# CHECON_PCB_Button.net
KiCad netlist of a schematic drawn in EAGLE
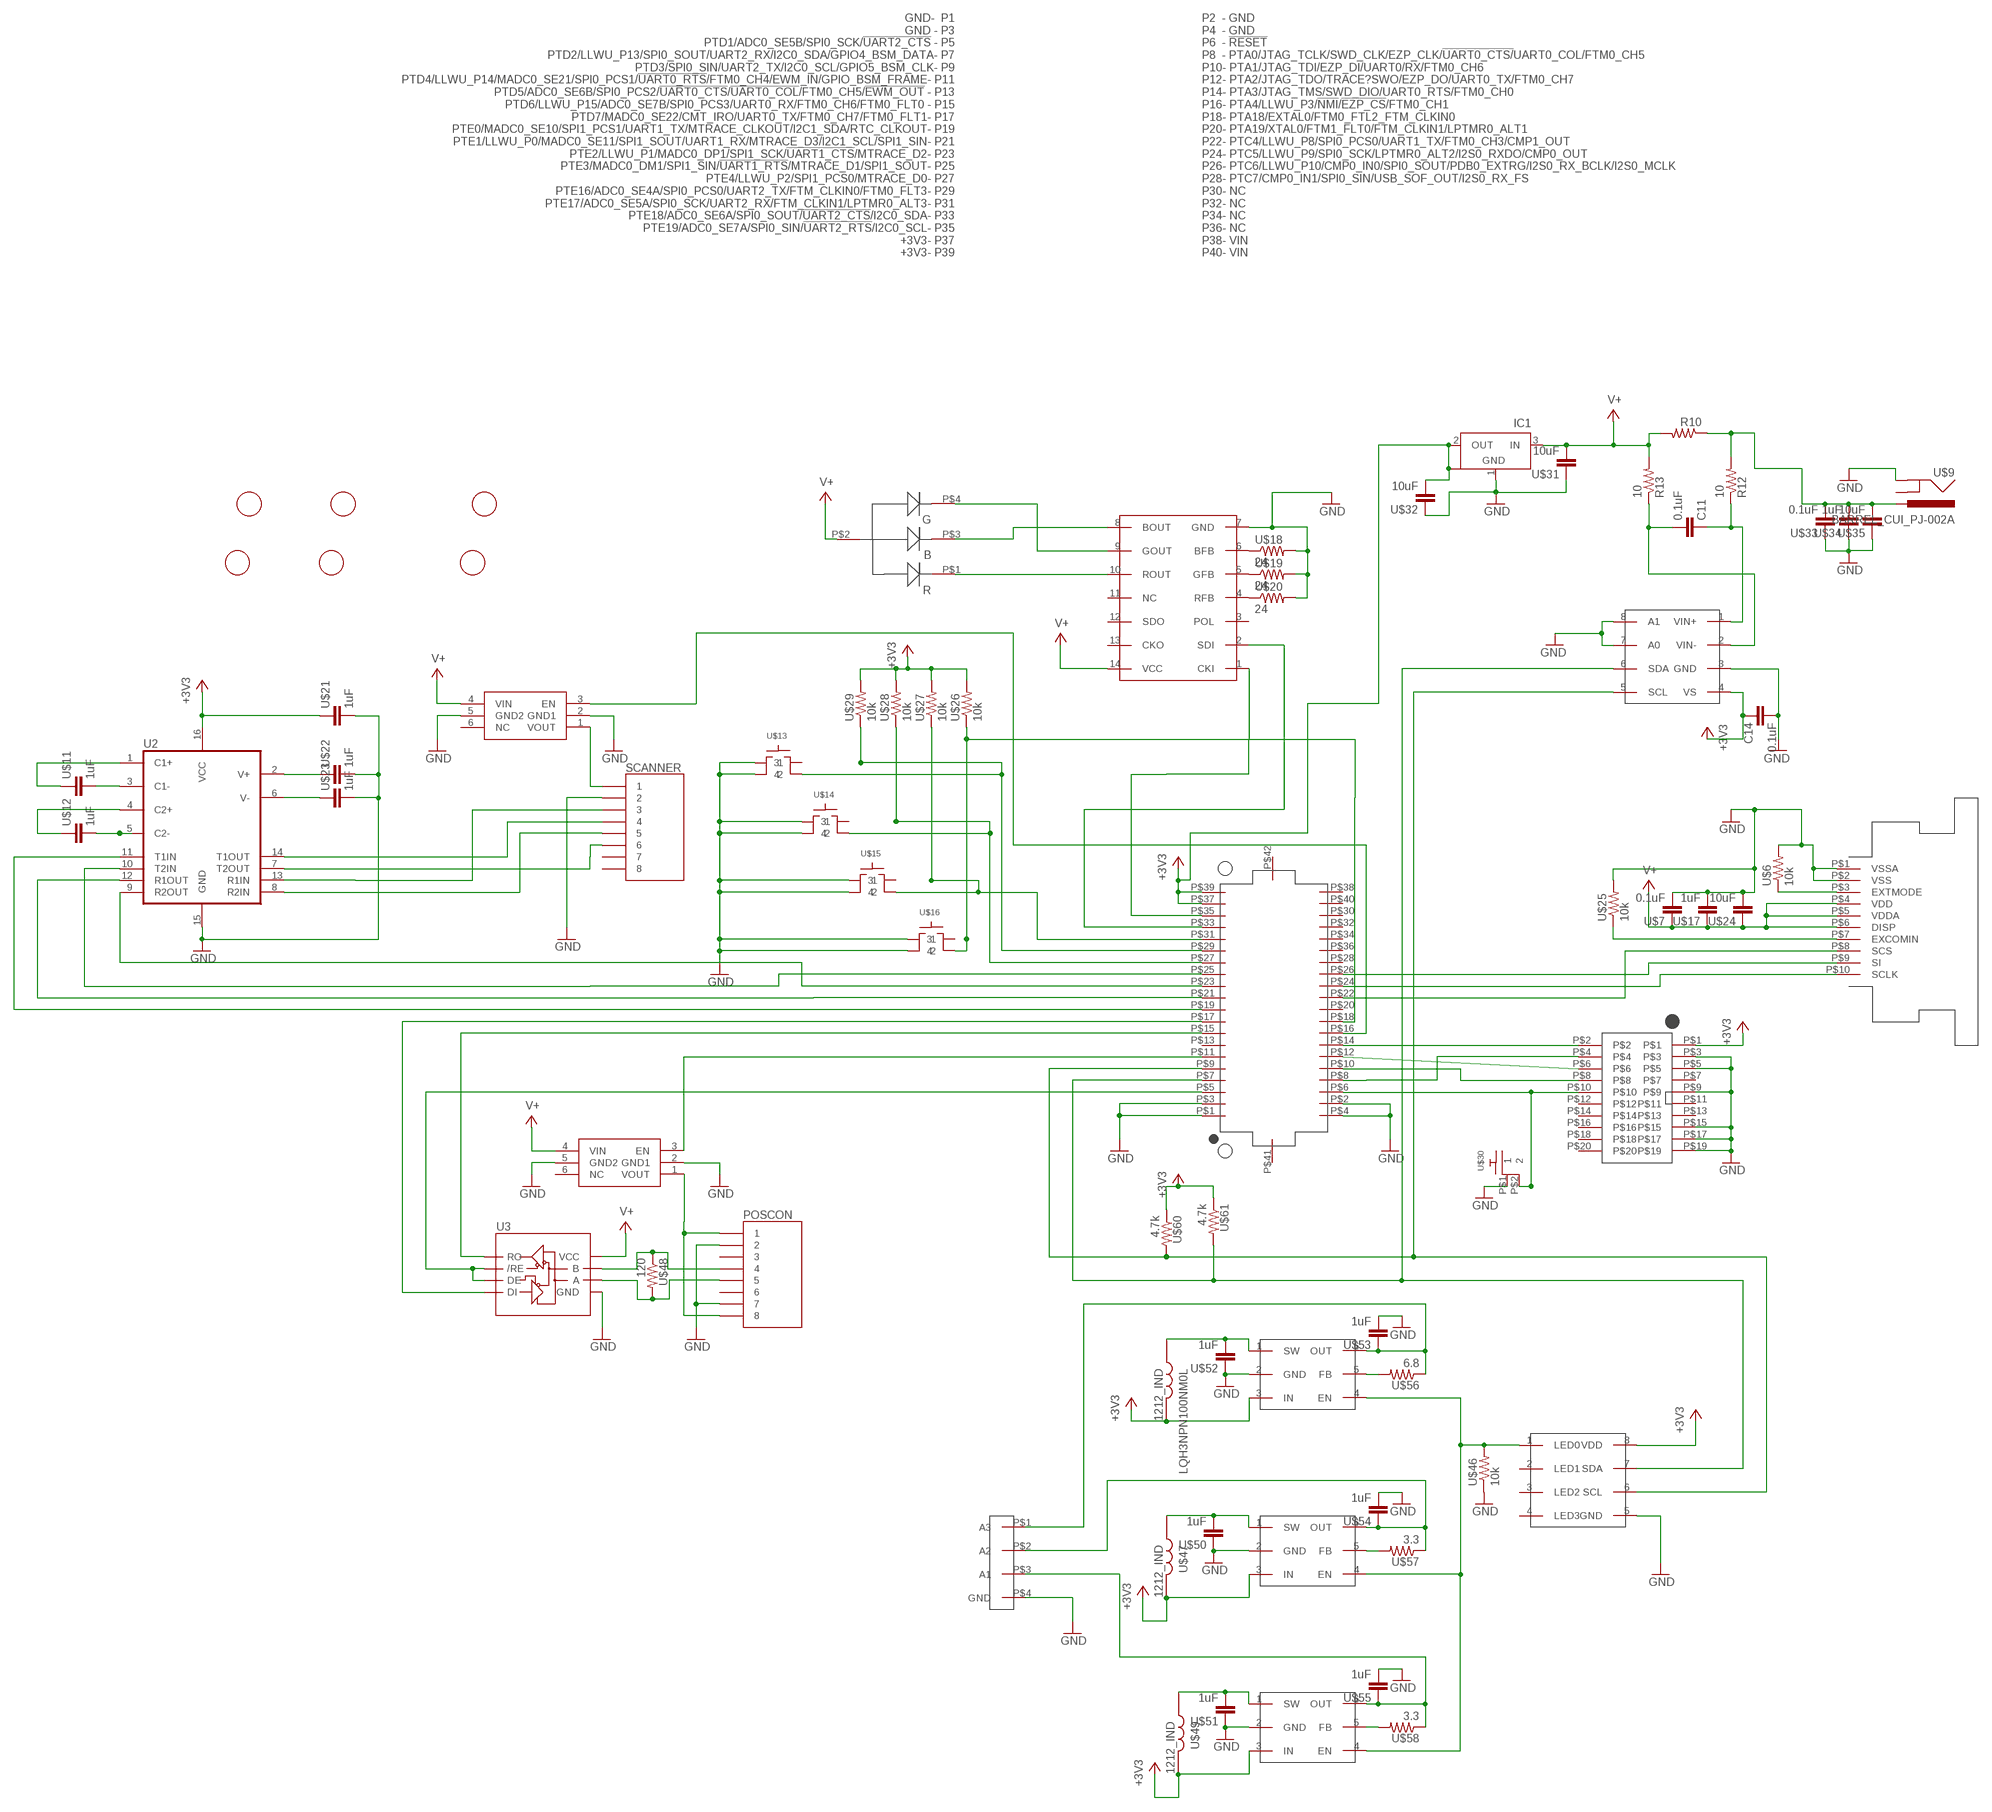
[diagram p0: schematic, sheet 1]

(export (version "E")
  (design (tool "Eeschema 10.0.6"))
  (components
    (comp (ref "C11")
      (value "0.1uF")
      (footprint "eagle-import:C0805")
      (libsource (lib "eagle-import") (part "RF-C0805"))
    )
    (comp (ref "C14")
      (value "0.1uF")
      (footprint "eagle-import:C0805")
      (libsource (lib "eagle-import") (part "RF-C0805"))
    )
    (comp (ref "IC1")
      (value "NCP1117ST33T3G_1")
      (footprint "eagle-import:SOT223")
      (libsource (lib "eagle-import") (part "NCP1117ST33T3G_1"))
    )
    (comp (ref "LQH3NPN100NM0L")
      (value "1212_IND")
      (footprint "eagle-import:1212_IND")
      (libsource (lib "eagle-import") (part "1212_IND"))
    )
    (comp (ref "POSCON")
      (value "RJ45-8")
      (footprint "eagle-import:RJ45_SMD")
      (fields (field (name "MFGN") "Molex") (field (name "MFGP") "0955016889"))
      (libsource (lib "eagle-import") (part "RJ45-8"))
    )
    (comp (ref "R10")
      (value "RF-R2512")
      (footprint "eagle-import:R2512")
      (libsource (lib "eagle-import") (part "RF-R2512"))
    )
    (comp (ref "R12")
      (value "10")
      (footprint "eagle-import:RF-C0805")
      (libsource (lib "eagle-import") (part "RF-R0805"))
    )
    (comp (ref "R13")
      (value "10")
      (footprint "eagle-import:RF-C0805")
      (libsource (lib "eagle-import") (part "RF-R0805"))
    )
    (comp (ref "SCANNER")
      (value "RJ45-8")
      (footprint "eagle-import:RJ45_SMD")
      (fields (field (name "MFGP") "0955016889"))
      (libsource (lib "eagle-import") (part "RJ45-8"))
    )
    (comp (ref "U$1")
      (value "RGLBED")
      (footprint "eagle-import:RGBLED")
      (libsource (lib "eagle-import") (part "RGLBED"))
    )
    (comp (ref "U$2")
      (value "52745-1097")
      (footprint "eagle-import:52745-1097")
      (libsource (lib "eagle-import") (part "52745-1097"))
    )
    (comp (ref "U$3")
      (value "2X10JTAG")
      (footprint "eagle-import:2X10JTAG")
      (libsource (lib "eagle-import") (part "2X10JTAG"))
    )
    (comp (ref "U$4")
      (value "MIC94061C6")
      (footprint "eagle-import:SC70-6L")
      (libsource (lib "eagle-import") (part "MIC94061C6"))
    )
    (comp (ref "U$5")
      (value "MIC94061C6")
      (footprint "eagle-import:SC70-6L")
      (libsource (lib "eagle-import") (part "MIC94061C6"))
    )
    (comp (ref "U$6")
      (value "10k")
      (footprint "eagle-import:RF-C0805")
      (libsource (lib "eagle-import") (part "RF-R0805"))
    )
    (comp (ref "U$7")
      (value "0.1uF")
      (footprint "eagle-import:C0805")
      (libsource (lib "eagle-import") (part "RF-C0805"))
    )
    (comp (ref "U$8")
      (value "WS2801")
      (footprint "eagle-import:SO14")
      (fields (field (name "MFGP") "WS2801"))
      (libsource (lib "eagle-import") (part "WS2801"))
    )
    (comp (ref "U$9")
      (value "BARREL_CUI_PJ-002A")
      (footprint "eagle-import:BARREL_CUI_PJ-002A")
      (libsource (lib "eagle-import") (part "BARREL_CUI_PJ-002A"))
    )
    (comp (ref "U$10")
      (value "KW2_CPU_COMBO")
      (footprint "eagle-import:BRAIN_COMBO")
      (libsource (lib "eagle-import") (part "KW2_CPU_COMBO"))
    )
    (comp (ref "U$11")
      (value "1uF")
      (footprint "eagle-import:C0805")
      (libsource (lib "eagle-import") (part "RF-C0805"))
    )
    (comp (ref "U$12")
      (value "1uF")
      (footprint "eagle-import:C0805")
      (libsource (lib "eagle-import") (part "RF-C0805"))
    )
    (comp (ref "U$13")
      (value "SWITCH-TACTILE-FSM")
      (footprint "eagle-import:SWITCH-TACTILE-FSM")
      (libsource (lib "eagle-import") (part "SWITCH-TACTILE-FSM"))
    )
    (comp (ref "U$14")
      (value "SWITCH-TACTILE-FSM")
      (footprint "eagle-import:SWITCH-TACTILE-FSM")
      (libsource (lib "eagle-import") (part "SWITCH-TACTILE-FSM"))
    )
    (comp (ref "U$15")
      (value "SWITCH-TACTILE-FSM")
      (footprint "eagle-import:SWITCH-TACTILE-FSM")
      (libsource (lib "eagle-import") (part "SWITCH-TACTILE-FSM"))
    )
    (comp (ref "U$16")
      (value "SWITCH-TACTILE-FSM")
      (footprint "eagle-import:SWITCH-TACTILE-FSM")
      (libsource (lib "eagle-import") (part "SWITCH-TACTILE-FSM"))
    )
    (comp (ref "U$17")
      (value "1uF")
      (footprint "eagle-import:C0805")
      (libsource (lib "eagle-import") (part "RF-C0805"))
    )
    (comp (ref "U$18")
      (value "24")
      (footprint "eagle-import:RF-C0805")
      (libsource (lib "eagle-import") (part "RF-R0805"))
    )
    (comp (ref "U$19")
      (value "24")
      (footprint "eagle-import:RF-C0805")
      (libsource (lib "eagle-import") (part "RF-R0805"))
    )
    (comp (ref "U$20")
      (value "24")
      (footprint "eagle-import:RF-C0805")
      (libsource (lib "eagle-import") (part "RF-R0805"))
    )
    (comp (ref "U$21")
      (value "1uF")
      (footprint "eagle-import:C0805")
      (libsource (lib "eagle-import") (part "RF-C0805"))
    )
    (comp (ref "U$22")
      (value "1uF")
      (footprint "eagle-import:C0805")
      (libsource (lib "eagle-import") (part "RF-C0805"))
    )
    (comp (ref "U$23")
      (value "1uF")
      (footprint "eagle-import:C0805")
      (libsource (lib "eagle-import") (part "RF-C0805"))
    )
    (comp (ref "U$24")
      (value "10uF")
      (footprint "eagle-import:C0805")
      (libsource (lib "eagle-import") (part "RF-C0805"))
    )
    (comp (ref "U$25")
      (value "10k")
      (footprint "eagle-import:RF-C0805")
      (libsource (lib "eagle-import") (part "RF-R0805"))
    )
    (comp (ref "U$26")
      (value "10k")
      (footprint "eagle-import:RF-C0805")
      (libsource (lib "eagle-import") (part "RF-R0805"))
    )
    (comp (ref "U$27")
      (value "10k")
      (footprint "eagle-import:RF-C0805")
      (libsource (lib "eagle-import") (part "RF-R0805"))
    )
    (comp (ref "U$28")
      (value "10k")
      (footprint "eagle-import:RF-C0805")
      (libsource (lib "eagle-import") (part "RF-R0805"))
    )
    (comp (ref "U$29")
      (value "10k")
      (footprint "eagle-import:RF-C0805")
      (libsource (lib "eagle-import") (part "RF-R0805"))
    )
    (comp (ref "U$30")
      (value "RA_BUTTON")
      (footprint "eagle-import:RA_BUTTON")
      (libsource (lib "eagle-import") (part "RA_BUTTON"))
    )
    (comp (ref "U$31")
      (value "10uF")
      (footprint "eagle-import:C0805")
      (libsource (lib "eagle-import") (part "RF-C0805"))
    )
    (comp (ref "U$32")
      (value "10uF")
      (footprint "eagle-import:C0805")
      (libsource (lib "eagle-import") (part "RF-C0805"))
    )
    (comp (ref "U$33")
      (value "0.1uF")
      (footprint "eagle-import:C0805")
      (libsource (lib "eagle-import") (part "RF-C0805"))
    )
    (comp (ref "U$34")
      (value "1uF")
      (footprint "eagle-import:C0805")
      (libsource (lib "eagle-import") (part "RF-C0805"))
    )
    (comp (ref "U$35")
      (value "10uF")
      (footprint "eagle-import:C0805")
      (libsource (lib "eagle-import") (part "RF-C0805"))
    )
    (comp (ref "U$36")
      (value "SC4541")
      (footprint "eagle-import:SOT23-6")
      (libsource (lib "eagle-import") (part "SC4541"))
    )
    (comp (ref "U$37")
      (value "SC4541")
      (footprint "eagle-import:SOT23-6")
      (libsource (lib "eagle-import") (part "SC4541"))
    )
    (comp (ref "U$38")
      (value "FIDUCIAL")
      (footprint "eagle-import:FIDUCIAL_1MM")
      (libsource (lib "eagle-import") (part "FIDUCIAL"))
    )
    (comp (ref "U$39")
      (value "FIDUCIAL")
      (footprint "eagle-import:FIDUCIAL_1MM")
      (libsource (lib "eagle-import") (part "FIDUCIAL"))
    )
    (comp (ref "U$40")
      (value "FIDUCIAL")
      (footprint "eagle-import:FIDUCIAL_1MM")
      (libsource (lib "eagle-import") (part "FIDUCIAL"))
    )
    (comp (ref "U$41")
      (value "FIDUCIAL")
      (footprint "eagle-import:FIDUCIAL_1MM")
      (libsource (lib "eagle-import") (part "FIDUCIAL"))
    )
    (comp (ref "U$42")
      (value "FIDUCIAL")
      (footprint "eagle-import:FIDUCIAL_1MM")
      (libsource (lib "eagle-import") (part "FIDUCIAL"))
    )
    (comp (ref "U$43")
      (value "FIDUCIAL")
      (footprint "eagle-import:FIDUCIAL_1MM")
      (libsource (lib "eagle-import") (part "FIDUCIAL"))
    )
    (comp (ref "U$44")
      (value "SC4541")
      (footprint "eagle-import:SOT23-6")
      (libsource (lib "eagle-import") (part "SC4541"))
    )
    (comp (ref "U$45")
      (value "PCA9632DP1")
      (footprint "eagle-import:TSSOP-8")
      (libsource (lib "eagle-import") (part "PCA9632DP1"))
    )
    (comp (ref "U$46")
      (value "10k")
      (footprint "eagle-import:RF-C0805")
      (libsource (lib "eagle-import") (part "RF-R0805"))
    )
    (comp (ref "U$47")
      (value "1212_IND")
      (footprint "eagle-import:1212_IND")
      (libsource (lib "eagle-import") (part "1212_IND"))
    )
    (comp (ref "U$48")
      (value "120")
      (footprint "eagle-import:RF-C0805")
      (libsource (lib "eagle-import") (part "RF-R0805"))
    )
    (comp (ref "U$49")
      (value "1212_IND")
      (footprint "eagle-import:1212_IND")
      (libsource (lib "eagle-import") (part "1212_IND"))
    )
    (comp (ref "U$50")
      (value "1uF")
      (footprint "eagle-import:C0805")
      (libsource (lib "eagle-import") (part "RF-C0805"))
    )
    (comp (ref "U$51")
      (value "1uF")
      (footprint "eagle-import:C0805")
      (libsource (lib "eagle-import") (part "RF-C0805"))
    )
    (comp (ref "U$52")
      (value "1uF")
      (footprint "eagle-import:C0805")
      (libsource (lib "eagle-import") (part "RF-C0805"))
    )
    (comp (ref "U$53")
      (value "1uF")
      (footprint "eagle-import:C0805")
      (libsource (lib "eagle-import") (part "RF-C0805"))
    )
    (comp (ref "U$54")
      (value "1uF")
      (footprint "eagle-import:C0805")
      (libsource (lib "eagle-import") (part "RF-C0805"))
    )
    (comp (ref "U$55")
      (value "1uF")
      (footprint "eagle-import:C0805")
      (libsource (lib "eagle-import") (part "RF-C0805"))
    )
    (comp (ref "U$56")
      (value "6.8")
      (footprint "eagle-import:RF-C0805")
      (libsource (lib "eagle-import") (part "RF-R0805"))
    )
    (comp (ref "U$57")
      (value "3.3")
      (footprint "eagle-import:RF-C0805")
      (libsource (lib "eagle-import") (part "RF-R0805"))
    )
    (comp (ref "U$58")
      (value "3.3")
      (footprint "eagle-import:RF-C0805")
      (libsource (lib "eagle-import") (part "RF-R0805"))
    )
    (comp (ref "U$59")
      (value "BL_CON")
      (footprint "eagle-import:009155004301006")
      (libsource (lib "eagle-import") (part "BL_CON"))
    )
    (comp (ref "U$60")
      (value "4.7k")
      (footprint "eagle-import:RF-C0805")
      (libsource (lib "eagle-import") (part "RF-R0805"))
    )
    (comp (ref "U$61")
      (value "4.7k")
      (footprint "eagle-import:RF-C0805")
      (libsource (lib "eagle-import") (part "RF-R0805"))
    )
    (comp (ref "U$62")
      (value "INA219B")
      (footprint "eagle-import:DCN-R-PDSO-G8")
      (libsource (lib "eagle-import") (part "INA219B"))
    )
    (comp (ref "U2")
      (value "MAX232SOIC16")
      (footprint "eagle-import:SO016")
      (fields (field (name "MFGP") "MAX232DR"))
      (libsource (lib "eagle-import") (part "MAX232SOIC16"))
    )
    (comp (ref "U3")
      (value "RS485SOIC")
      (footprint "eagle-import:SO08")
      (fields (field (name "MFGP") "SN65HVD1781DR"))
      (libsource (lib "eagle-import") (part "RS485SOIC"))
    )
  )
  (nets
    (net (code "1") (name "+3V3") (class "Default")
      (node (ref "C14") (pin "1") (pinfunction "1_1") (pintype "passive"))
      (node (ref "IC1") (pin "2") (pinfunction "OUT_2") (pintype "power_in"))
      (node (ref "IC1") (pin "4") (pinfunction "OUT1_4") (pintype "power_in"))
      (node (ref "LQH3NPN100NM0L") (pin "P$1") (pinfunction "1_P$1") (pintype "bidirectional"))
      (node (ref "U$10") (pin "P$37") (pinfunction "+3V3_P$37") (pintype "bidirectional"))
      (node (ref "U$10") (pin "P$39") (pinfunction "+3V3_P$39") (pintype "bidirectional"))
      (node (ref "U$21") (pin "1") (pinfunction "1_1") (pintype "passive"))
      (node (ref "U$26") (pin "2") (pinfunction "2_2") (pintype "passive"))
      (node (ref "U$27") (pin "2") (pinfunction "2_2") (pintype "passive"))
      (node (ref "U$28") (pin "2") (pinfunction "2_2") (pintype "passive"))
      (node (ref "U$29") (pin "2") (pinfunction "2_2") (pintype "passive"))
      (node (ref "U$3") (pin "P$1") (pinfunction "P$1_P$1") (pintype "bidirectional"))
      (node (ref "U$32") (pin "2") (pinfunction "2_2") (pintype "passive"))
      (node (ref "U$36") (pin "3") (pinfunction "IN_3") (pintype "bidirectional"))
      (node (ref "U$37") (pin "3") (pinfunction "IN_3") (pintype "bidirectional"))
      (node (ref "U$44") (pin "3") (pinfunction "IN_3") (pintype "bidirectional"))
      (node (ref "U$45") (pin "8") (pinfunction "VDD_8") (pintype "bidirectional"))
      (node (ref "U$47") (pin "P$1") (pinfunction "1_P$1") (pintype "bidirectional"))
      (node (ref "U$49") (pin "P$1") (pinfunction "1_P$1") (pintype "bidirectional"))
      (node (ref "U$60") (pin "1") (pinfunction "1_1") (pintype "passive"))
      (node (ref "U$61") (pin "1") (pinfunction "1_1") (pintype "passive"))
      (node (ref "U$62") (pin "4") (pinfunction "VS_4") (pintype "bidirectional"))
      (node (ref "U2") (pin "16") (pinfunction "VCC_16") (pintype "bidirectional"))
    )
    (net (code "2") (name "GND") (class "Default")
      (node (ref "C14") (pin "2") (pinfunction "2_2") (pintype "passive"))
      (node (ref "IC1") (pin "1") (pinfunction "GND_1") (pintype "power_in"))
      (node (ref "POSCON") (pin "P$2") (pinfunction "2_P$2") (pintype "bidirectional"))
      (node (ref "POSCON") (pin "P$7") (pinfunction "7_P$7") (pintype "bidirectional"))
      (node (ref "SCANNER") (pin "P$2") (pinfunction "2_P$2") (pintype "bidirectional"))
      (node (ref "U$10") (pin "P$1") (pinfunction "GND_P$1") (pintype "bidirectional"))
      (node (ref "U$10") (pin "P$2") (pinfunction "GND_P$2") (pintype "bidirectional"))
      (node (ref "U$10") (pin "P$3") (pinfunction "GND_P$3") (pintype "bidirectional"))
      (node (ref "U$10") (pin "P$4") (pinfunction "GND_P$4") (pintype "bidirectional"))
      (node (ref "U$13") (pin "P$1") (pinfunction "1_P$1") (pintype "input"))
      (node (ref "U$13") (pin "P$2") (pinfunction "2_P$2") (pintype "input"))
      (node (ref "U$14") (pin "P$1") (pinfunction "1_P$1") (pintype "input"))
      (node (ref "U$14") (pin "P$2") (pinfunction "2_P$2") (pintype "input"))
      (node (ref "U$15") (pin "P$1") (pinfunction "1_P$1") (pintype "input"))
      (node (ref "U$15") (pin "P$2") (pinfunction "2_P$2") (pintype "input"))
      (node (ref "U$16") (pin "P$1") (pinfunction "1_P$1") (pintype "input"))
      (node (ref "U$16") (pin "P$2") (pinfunction "2_P$2") (pintype "input"))
      (node (ref "U$17") (pin "2") (pinfunction "2_2") (pintype "passive"))
      (node (ref "U$18") (pin "2") (pinfunction "2_2") (pintype "passive"))
      (node (ref "U$19") (pin "2") (pinfunction "2_2") (pintype "passive"))
      (node (ref "U$2") (pin "P$1") (pinfunction "VSSA_P$1") (pintype "bidirectional"))
      (node (ref "U$2") (pin "P$2") (pinfunction "VSS_P$2") (pintype "bidirectional"))
      (node (ref "U$20") (pin "2") (pinfunction "2_2") (pintype "passive"))
      (node (ref "U$21") (pin "2") (pinfunction "2_2") (pintype "passive"))
      (node (ref "U$22") (pin "2") (pinfunction "2_2") (pintype "passive"))
      (node (ref "U$23") (pin "2") (pinfunction "2_2") (pintype "passive"))
      (node (ref "U$24") (pin "2") (pinfunction "2_2") (pintype "passive"))
      (node (ref "U$25") (pin "2") (pinfunction "2_2") (pintype "passive"))
      (node (ref "U$3") (pin "P$15") (pinfunction "P$15_P$15") (pintype "bidirectional"))
      (node (ref "U$3") (pin "P$17") (pinfunction "P$17_P$17") (pintype "bidirectional"))
      (node (ref "U$3") (pin "P$19") (pinfunction "P$19_P$19") (pintype "bidirectional"))
      (node (ref "U$3") (pin "P$3") (pinfunction "P$3_P$3") (pintype "bidirectional"))
      (node (ref "U$3") (pin "P$5") (pinfunction "P$5_P$5") (pintype "bidirectional"))
      (node (ref "U$3") (pin "P$9") (pinfunction "P$9_P$9") (pintype "bidirectional"))
      (node (ref "U$30") (pin "P$1") (pinfunction "1_P$1") (pintype "input"))
      (node (ref "U$31") (pin "1") (pinfunction "1_1") (pintype "passive"))
      (node (ref "U$32") (pin "1") (pinfunction "1_1") (pintype "passive"))
      (node (ref "U$33") (pin "1") (pinfunction "1_1") (pintype "passive"))
      (node (ref "U$34") (pin "1") (pinfunction "1_1") (pintype "passive"))
      (node (ref "U$35") (pin "1") (pinfunction "1_1") (pintype "passive"))
      (node (ref "U$36") (pin "2") (pinfunction "GND_2") (pintype "bidirectional"))
      (node (ref "U$37") (pin "2") (pinfunction "GND_2") (pintype "bidirectional"))
      (node (ref "U$4") (pin "2") (pinfunction "GND1_2") (pintype "bidirectional"))
      (node (ref "U$4") (pin "5") (pinfunction "GND2_5") (pintype "bidirectional"))
      (node (ref "U$44") (pin "2") (pinfunction "GND_2") (pintype "bidirectional"))
      (node (ref "U$45") (pin "5") (pinfunction "GND_5") (pintype "bidirectional"))
      (node (ref "U$46") (pin "1") (pinfunction "1_1") (pintype "passive"))
      (node (ref "U$5") (pin "2") (pinfunction "GND1_2") (pintype "bidirectional"))
      (node (ref "U$5") (pin "5") (pinfunction "GND2_5") (pintype "bidirectional"))
      (node (ref "U$50") (pin "1") (pinfunction "1_1") (pintype "passive"))
      (node (ref "U$51") (pin "1") (pinfunction "1_1") (pintype "passive"))
      (node (ref "U$52") (pin "1") (pinfunction "1_1") (pintype "passive"))
      (node (ref "U$53") (pin "2") (pinfunction "2_2") (pintype "passive"))
      (node (ref "U$54") (pin "2") (pinfunction "2_2") (pintype "passive"))
      (node (ref "U$55") (pin "2") (pinfunction "2_2") (pintype "passive"))
      (node (ref "U$59") (pin "P$4") (pinfunction "GND_P$4") (pintype "bidirectional"))
      (node (ref "U$6") (pin "2") (pinfunction "2_2") (pintype "passive"))
      (node (ref "U$62") (pin "3") (pinfunction "GND_3") (pintype "bidirectional"))
      (node (ref "U$62") (pin "7") (pinfunction "A0_7") (pintype "bidirectional"))
      (node (ref "U$62") (pin "8") (pinfunction "A1_8") (pintype "bidirectional"))
      (node (ref "U$7") (pin "2") (pinfunction "2_2") (pintype "passive"))
      (node (ref "U$8") (pin "7") (pinfunction "GND_7") (pintype "bidirectional"))
      (node (ref "U$9") (pin "P$2") (pinfunction "GND_P$2") (pintype "bidirectional"))
      (node (ref "U2") (pin "15") (pinfunction "GND_15") (pintype "bidirectional"))
      (node (ref "U3") (pin "5") (pinfunction "GND_5") (pintype "bidirectional"))
    )
    (net (code "3") (name "Net-(LQH3NPN100NM0L-2)") (class "Default")
      (node (ref "LQH3NPN100NM0L") (pin "P$2") (pinfunction "2_P$2") (pintype "bidirectional"))
      (node (ref "U$36") (pin "1") (pinfunction "SW_1") (pintype "bidirectional"))
      (node (ref "U$52") (pin "2") (pinfunction "2_2") (pintype "passive"))
    )
    (net (code "4") (name "Net-(POSCON-1)") (class "Default")
      (node (ref "POSCON") (pin "P$1") (pinfunction "1_P$1") (pintype "bidirectional"))
      (node (ref "POSCON") (pin "P$8") (pinfunction "8_P$8") (pintype "bidirectional"))
      (node (ref "U$5") (pin "1") (pinfunction "VOUT_1") (pintype "bidirectional"))
    )
    (net (code "5") (name "Net-(POSCON-4)") (class "Default")
      (node (ref "POSCON") (pin "P$4") (pinfunction "4_P$4") (pintype "bidirectional"))
      (node (ref "U$48") (pin "1") (pinfunction "1_1") (pintype "passive"))
      (node (ref "U3") (pin "7") (pinfunction "B_7") (pintype "bidirectional"))
    )
    (net (code "6") (name "Net-(POSCON-5)") (class "Default")
      (node (ref "POSCON") (pin "P$5") (pinfunction "5_P$5") (pintype "bidirectional"))
      (node (ref "U$48") (pin "2") (pinfunction "2_2") (pintype "passive"))
      (node (ref "U3") (pin "6") (pinfunction "A_6") (pintype "bidirectional"))
    )
    (net (code "7") (name "Net-(SCANNER-1)") (class "Default")
      (node (ref "SCANNER") (pin "P$1") (pinfunction "1_P$1") (pintype "bidirectional"))
      (node (ref "U$4") (pin "1") (pinfunction "VOUT_1") (pintype "bidirectional"))
    )
    (net (code "8") (name "Net-(SCANNER-3)") (class "Default")
      (node (ref "SCANNER") (pin "P$3") (pinfunction "3_P$3") (pintype "bidirectional"))
      (node (ref "U2") (pin "13") (pinfunction "R1IN_13") (pintype "input"))
    )
    (net (code "9") (name "Net-(SCANNER-4)") (class "Default")
      (node (ref "SCANNER") (pin "P$4") (pinfunction "4_P$4") (pintype "bidirectional"))
      (node (ref "U2") (pin "14") (pinfunction "T1OUT_14") (pintype "output"))
    )
    (net (code "10") (name "Net-(SCANNER-5)") (class "Default")
      (node (ref "SCANNER") (pin "P$5") (pinfunction "5_P$5") (pintype "bidirectional"))
      (node (ref "U2") (pin "8") (pinfunction "R2IN_8") (pintype "input"))
    )
    (net (code "11") (name "Net-(SCANNER-6)") (class "Default")
      (node (ref "SCANNER") (pin "P$6") (pinfunction "6_P$6") (pintype "bidirectional"))
      (node (ref "U2") (pin "7") (pinfunction "T2OUT_7") (pintype "output"))
    )
    (net (code "12") (name "Net-(U$1-BLUE)") (class "Default")
      (node (ref "U$1") (pin "P$3") (pinfunction "BLUE_P$3") (pintype "bidirectional"))
      (node (ref "U$8") (pin "8") (pinfunction "BOUT_8") (pintype "bidirectional"))
    )
    (net (code "13") (name "Net-(U$1-GREEN)") (class "Default")
      (node (ref "U$1") (pin "P$4") (pinfunction "GREEN_P$4") (pintype "bidirectional"))
      (node (ref "U$8") (pin "9") (pinfunction "GOUT_9") (pintype "bidirectional"))
    )
    (net (code "14") (name "Net-(U$1-RED)") (class "Default")
      (node (ref "U$1") (pin "P$1") (pinfunction "RED_P$1") (pintype "bidirectional"))
      (node (ref "U$8") (pin "10") (pinfunction "ROUT_10") (pintype "bidirectional"))
    )
    (net (code "15") (name "Net-(U$2-EXCOMIN)") (class "Default")
      (node (ref "U$2") (pin "P$7") (pinfunction "EXCOMIN_P$7") (pintype "bidirectional"))
      (node (ref "U$25") (pin "1") (pinfunction "1_1") (pintype "passive"))
    )
    (net (code "16") (name "Net-(U$2-EXTMODE)") (class "Default")
      (node (ref "U$2") (pin "P$3") (pinfunction "EXTMODE_P$3") (pintype "bidirectional"))
      (node (ref "U$6") (pin "1") (pinfunction "1_1") (pintype "passive"))
    )
    (net (code "17") (name "Net-(U$8-BFB)") (class "Default")
      (node (ref "U$18") (pin "1") (pinfunction "1_1") (pintype "passive"))
      (node (ref "U$8") (pin "6") (pinfunction "BFB_6") (pintype "bidirectional"))
    )
    (net (code "18") (name "Net-(U$8-GFB)") (class "Default")
      (node (ref "U$19") (pin "1") (pinfunction "1_1") (pintype "passive"))
      (node (ref "U$8") (pin "5") (pinfunction "GFB_5") (pintype "bidirectional"))
    )
    (net (code "19") (name "Net-(U$8-RFB)") (class "Default")
      (node (ref "U$20") (pin "1") (pinfunction "1_1") (pintype "passive"))
      (node (ref "U$8") (pin "4") (pinfunction "RFB_4") (pintype "bidirectional"))
    )
    (net (code "20") (name "Net-(U$9-PWR)") (class "Default")
      (node (ref "R10") (pin "1") (pinfunction "1_1") (pintype "passive"))
      (node (ref "R12") (pin "2") (pinfunction "2_2") (pintype "passive"))
      (node (ref "U$33") (pin "2") (pinfunction "2_2") (pintype "passive"))
      (node (ref "U$34") (pin "2") (pinfunction "2_2") (pintype "passive"))
      (node (ref "U$35") (pin "2") (pinfunction "2_2") (pintype "passive"))
      (node (ref "U$9") (pin "P$1") (pinfunction "PWR_P$1") (pintype "bidirectional"))
    )
    (net (code "21") (name "Net-(U$10-PTA0{slash}JTAG_TCLK{slash}SWD_CLK{slash}EZP_CLK{slash}~{UART0_CTS{slash}}UART0_COL{slash}FTM0_CH5)") (class "Default")
      (node (ref "U$10") (pin "P$8") (pinfunction "PTA0/JTAG_TCLK/SWD_CLK/EZP_CLK/~{UART0_CTS/}UART0_COL/FTM0_CH5_P$8") (pintype "bidirectional"))
      (node (ref "U$3") (pin "P$4") (pinfunction "P$4_P$4") (pintype "bidirectional"))
    )
    (net (code "22") (name "Net-(U$10-PTA1{slash}JTAG_TDI{slash}EZP_DI{slash}UART0{slash}RX{slash}FTM0_CH6)") (class "Default")
      (node (ref "U$10") (pin "P$10") (pinfunction "PTA1/JTAG_TDI/EZP_DI/UART0/RX/FTM0_CH6_P$10") (pintype "bidirectional"))
      (node (ref "U$3") (pin "P$8") (pinfunction "P$8_P$8") (pintype "bidirectional"))
    )
    (net (code "23") (name "Net-(U$10-PTA2{slash}JTAG_TDO{slash}TRACE?SWO{slash}EZP_DO{slash}UART0_TX{slash}FTM0_CH7)") (class "Default")
      (node (ref "U$10") (pin "P$12") (pinfunction "PTA2/JTAG_TDO/TRACE?SWO/EZP_DO/UART0_TX/FTM0_CH7_P$12") (pintype "bidirectional"))
      (node (ref "U$3") (pin "P$6") (pinfunction "P$6_P$6") (pintype "bidirectional"))
    )
    (net (code "24") (name "Net-(U$10-PTA3{slash}JTAG_TMS{slash}SWD_DIO{slash}UART0_RTS{slash}FTM0_CH0)") (class "Default")
      (node (ref "U$10") (pin "P$14") (pinfunction "PTA3/JTAG_TMS/SWD_DIO/UART0_RTS/FTM0_CH0_P$14") (pintype "bidirectional"))
      (node (ref "U$3") (pin "P$2") (pinfunction "P$2_P$2") (pintype "bidirectional"))
    )
    (net (code "25") (name "Net-(U$10-PTA4{slash}LLWU_P3{slash}~{NMI}{slash}~{EZP_CS}{slash}FTM0_CH1)") (class "Default")
      (node (ref "U$10") (pin "P$16") (pinfunction "PTA4/LLWU_P3/~{NMI}/~{EZP_CS}/FTM0_CH1_P$16") (pintype "bidirectional"))
      (node (ref "U$4") (pin "3") (pinfunction "EN_3") (pintype "bidirectional"))
    )
    (net (code "26") (name "Net-(U$10-PTA18{slash}EXTAL0{slash}FTM0_FTL2_FTM_CLKIN0)") (class "Default")
      (node (ref "U$10") (pin "P$18") (pinfunction "PTA18/EXTAL0/FTM0_FTL2_FTM_CLKIN0_P$18") (pintype "bidirectional"))
      (node (ref "U$16") (pin "P$4") (pinfunction "4_P$4") (pintype "input"))
      (node (ref "U$26") (pin "1") (pinfunction "1_1") (pintype "passive"))
    )
    (net (code "27") (name "Net-(U$10-PTC4{slash}LLWU_P8{slash}SPI0_PCS0{slash}UART1_TX{slash}FTM0_CH3{slash}CMP1_OUT)") (class "Default")
      (node (ref "U$10") (pin "P$22") (pinfunction "PTC4/LLWU_P8/SPI0_PCS0/UART1_TX/FTM0_CH3/CMP1_OUT_P$22") (pintype "bidirectional"))
      (node (ref "U$2") (pin "P$8") (pinfunction "SCS_P$8") (pintype "bidirectional"))
    )
    (net (code "28") (name "Net-(U$10-PTC5{slash}LLWU_P8{slash}SPI0_PCS0{slash}UART1_TX{slash}FTM0_CH3{slash}CMP1_OUT)") (class "Default")
      (node (ref "U$10") (pin "P$24") (pinfunction "PTC5/LLWU_P8/SPI0_PCS0/UART1_TX/FTM0_CH3/CMP1_OUT_P$24") (pintype "bidirectional"))
      (node (ref "U$2") (pin "P$10") (pinfunction "SCLK_P$10") (pintype "bidirectional"))
    )
    (net (code "29") (name "Net-(U$10-PTC6{slash}LLWU_P10{slash}CMP0_IN0{slash}SPI0_SOUT{slash}PDB0_EXTRG{slash}I2S0_RX_BCLK{slash}I2S0_MCLK)") (class "Default")
      (node (ref "U$10") (pin "P$26") (pinfunction "PTC6/LLWU_P10/CMP0_IN0/SPI0_SOUT/PDB0_EXTRG/I2S0_RX_BCLK/I2S0_MCLK_P$26") (pintype "bidirectional"))
      (node (ref "U$2") (pin "P$9") (pinfunction "SI_P$9") (pintype "bidirectional"))
    )
    (net (code "30") (name "Net-(U$10-PTD1{slash}ADC0_SE5B{slash}SPI0_SCK{slash}~{UART2_CTS})") (class "Default")
      (node (ref "U$10") (pin "P$5") (pinfunction "PTD1/ADC0_SE5B/SPI0_SCK/~{UART2_CTS}_P$5") (pintype "bidirectional"))
      (node (ref "U3") (pin "2") (pinfunction "/RE_2") (pintype "bidirectional"))
      (node (ref "U3") (pin "3") (pinfunction "DE_3") (pintype "bidirectional"))
    )
    (net (code "31") (name "Net-(U$10-PTD2{slash}LLWU_P13{slash}SPI0_SOUT{slash}UART2_RX{slash}I2C0_SDA{slash}GPIO4_BSM_DATA)") (class "Default")
      (node (ref "U$10") (pin "P$7") (pinfunction "PTD2/LLWU_P13/SPI0_SOUT/UART2_RX/I2C0_SDA/GPIO4_BSM_DATA_P$7") (pintype "bidirectional"))
      (node (ref "U$45") (pin "7") (pinfunction "SDA_7") (pintype "bidirectional"))
      (node (ref "U$61") (pin "2") (pinfunction "2_2") (pintype "passive"))
      (node (ref "U$62") (pin "6") (pinfunction "SDA_6") (pintype "bidirectional"))
    )
    (net (code "32") (name "Net-(U$10-PTD3{slash}SPI0_SIN{slash}UART2_TX{slash}I2C0_SCL{slash}GPIO5_BSM_CLK)") (class "Default")
      (node (ref "U$10") (pin "P$9") (pinfunction "PTD3/SPI0_SIN/UART2_TX/I2C0_SCL/GPIO5_BSM_CLK_P$9") (pintype "bidirectional"))
      (node (ref "U$45") (pin "6") (pinfunction "SCL_6") (pintype "bidirectional"))
      (node (ref "U$60") (pin "2") (pinfunction "2_2") (pintype "passive"))
      (node (ref "U$62") (pin "5") (pinfunction "SCL_5") (pintype "bidirectional"))
    )
    (net (code "33") (name "Net-(U$10-PTD4{slash}LLWU_P14{slash}MADC0_SE21{slash}SPI0_PCS1{slash}~{UART0_RTS}{slash}FTM0_CH4{slash}EWM_IN{slash}GPIO_BSM_FRAME)") (class "Default")
      (node (ref "U$10") (pin "P$11") (pinfunction "PTD4/LLWU_P14/MADC0_SE21/SPI0_PCS1/~{UART0_RTS}/FTM0_CH4/EWM_IN/GPIO_BSM_FRAME_P$11") (pintype "bidirectional"))
      (node (ref "U$5") (pin "3") (pinfunction "EN_3") (pintype "bidirectional"))
    )
    (net (code "34") (name "Net-(U$10-PTD6{slash}LLWU_P15{slash}ADC0_SE7B{slash}SPI0_PCS3{slash}UART0_RX{slash}FTM0_CH6{slash}FTM0_FLT0)") (class "Default")
      (node (ref "U$10") (pin "P$15") (pinfunction "PTD6/LLWU_P15/ADC0_SE7B/SPI0_PCS3/UART0_RX/FTM0_CH6/FTM0_FLT0_P$15") (pintype "bidirectional"))
      (node (ref "U3") (pin "1") (pinfunction "RO_1") (pintype "bidirectional"))
    )
    (net (code "35") (name "Net-(U$10-PTD7{slash}MADC0_SE22{slash}CMT_IRO{slash}UART0_TX{slash}FTM0_CH7{slash}FTM0_FLT1)") (class "Default")
      (node (ref "U$10") (pin "P$17") (pinfunction "PTD7/MADC0_SE22/CMT_IRO/UART0_TX/FTM0_CH7/FTM0_FLT1_P$17") (pintype "bidirectional"))
      (node (ref "U3") (pin "4") (pinfunction "DI_4") (pintype "bidirectional"))
    )
    (net (code "36") (name "Net-(U$10-PTE0{slash}MADC0_SE10{slash}SPI1_PCS1{slash}UART1_TX{slash}MTRACE_CLKOUT{slash}I2C1_SDA{slash}RTC_CLKOUT)") (class "Default")
      (node (ref "U$10") (pin "P$19") (pinfunction "PTE0/MADC0_SE10/SPI1_PCS1/UART1_TX/MTRACE_CLKOUT/I2C1_SDA/RTC_CLKOUT_P$19") (pintype "bidirectional"))
      (node (ref "U2") (pin "11") (pinfunction "T1IN_11") (pintype "input"))
    )
    (net (code "37") (name "Net-(U$10-PTE1{slash}LLWU_P0{slash}MADC0_SE11{slash}SPI1_SOUT{slash}UART1_RX{slash}MTRACE_D3{slash}I2C1_SCL{slash}SPI1_SIN)") (class "Default")
      (node (ref "U$10") (pin "P$21") (pinfunction "PTE1/LLWU_P0/MADC0_SE11/SPI1_SOUT/UART1_RX/MTRACE_D3/I2C1_SCL/SPI1_SIN_P$21") (pintype "bidirectional"))
      (node (ref "U2") (pin "12") (pinfunction "R1OUT_12") (pintype "output"))
    )
    (net (code "38") (name "Net-(U$10-PTE2{slash}LLWU_P1{slash}MADC0_DP1{slash}SPI1_SCK{slash}~{UART1_CTS}{slash}MTRACE_D2)") (class "Default")
      (node (ref "U$10") (pin "P$23") (pinfunction "PTE2/LLWU_P1/MADC0_DP1/SPI1_SCK/~{UART1_CTS}/MTRACE_D2_P$23") (pintype "bidirectional"))
      (node (ref "U2") (pin "9") (pinfunction "R2OUT_9") (pintype "output"))
    )
    (net (code "39") (name "Net-(U$10-PTE3{slash}MADC0_DM1{slash}SPI1_SIN{slash}~{UART1_RTS}{slash}MTRACE_D1{slash}SPI1_SOUT)") (class "Default")
      (node (ref "U$10") (pin "P$25") (pinfunction "PTE3/MADC0_DM1/SPI1_SIN/~{UART1_RTS}/MTRACE_D1/SPI1_SOUT_P$25") (pintype "bidirectional"))
      (node (ref "U2") (pin "10") (pinfunction "T2IN_10") (pintype "input"))
    )
    (net (code "40") (name "Net-(U$10-PTE4{slash}LLWU_P2{slash}SPI1_PCS0{slash}MTRACE_D0)") (class "Default")
      (node (ref "U$10") (pin "P$27") (pinfunction "PTE4/LLWU_P2/SPI1_PCS0/MTRACE_D0_P$27") (pintype "bidirectional"))
      (node (ref "U$14") (pin "P$4") (pinfunction "4_P$4") (pintype "input"))
      (node (ref "U$28") (pin "1") (pinfunction "1_1") (pintype "passive"))
    )
    (net (code "41") (name "Net-(U$10-PTE16{slash}ADC0_SE4A{slash}SPI0_PCS0{slash}UART2_TX{slash}FTM_CLKIN0{slash}FTM0_FLT3)") (class "Default")
      (node (ref "U$10") (pin "P$29") (pinfunction "PTE16/ADC0_SE4A/SPI0_PCS0/UART2_TX/FTM_CLKIN0/FTM0_FLT3_P$29") (pintype "bidirectional"))
      (node (ref "U$13") (pin "P$4") (pinfunction "4_P$4") (pintype "input"))
      (node (ref "U$29") (pin "1") (pinfunction "1_1") (pintype "passive"))
    )
    (net (code "42") (name "Net-(U$10-PTE17{slash}ADC0_SE5A{slash}SPI0_SCK{slash}UART2_RX{slash}FTM_CLKIN1{slash}LPTMR0_ALT3)") (class "Default")
      (node (ref "U$10") (pin "P$31") (pinfunction "PTE17/ADC0_SE5A/SPI0_SCK/UART2_RX/FTM_CLKIN1/LPTMR0_ALT3_P$31") (pintype "bidirectional"))
      (node (ref "U$15") (pin "P$4") (pinfunction "4_P$4") (pintype "input"))
      (node (ref "U$27") (pin "1") (pinfunction "1_1") (pintype "passive"))
    )
    (net (code "43") (name "Net-(U$10-PTE18{slash}ADC0_SE6A{slash}SPI0_SOUT{slash}~{UART2_CTS}{slash}I2C0_SDA)") (class "Default")
      (node (ref "U$10") (pin "P$33") (pinfunction "PTE18/ADC0_SE6A/SPI0_SOUT/~{UART2_CTS}/I2C0_SDA_P$33") (pintype "bidirectional"))
      (node (ref "U$8") (pin "2") (pinfunction "SDI_2") (pintype "bidirectional"))
    )
    (net (code "44") (name "Net-(U$10-PTE19{slash}ADC0_SE7A{slash}SPI0_SIN{slash}~{UART2_RTS}{slash}I2C0_SCL)") (class "Default")
      (node (ref "U$10") (pin "P$35") (pinfunction "PTE19/ADC0_SE7A/SPI0_SIN/~{UART2_RTS}/I2C0_SCL_P$35") (pintype "bidirectional"))
      (node (ref "U$8") (pin "1") (pinfunction "CKI_1") (pintype "bidirectional"))
    )
    (net (code "45") (name "Net-(U$10-~{RESET})") (class "Default")
      (node (ref "U$10") (pin "P$6") (pinfunction "~{RESET}_P$6") (pintype "bidirectional"))
      (node (ref "U$3") (pin "P$10") (pinfunction "P$10_P$10") (pintype "bidirectional"))
      (node (ref "U$30") (pin "P$2") (pinfunction "2_P$2") (pintype "input"))
    )
    (net (code "46") (name "Net-(U$36-EN)") (class "Default")
      (node (ref "U$36") (pin "4") (pinfunction "EN_4") (pintype "bidirectional"))
      (node (ref "U$37") (pin "4") (pinfunction "EN_4") (pintype "bidirectional"))
      (node (ref "U$44") (pin "4") (pinfunction "EN_4") (pintype "bidirectional"))
      (node (ref "U$45") (pin "1") (pinfunction "LED0_1") (pintype "bidirectional"))
      (node (ref "U$46") (pin "2") (pinfunction "2_2") (pintype "passive"))
    )
    (net (code "47") (name "Net-(U$36-FB)") (class "Default")
      (node (ref "U$36") (pin "5") (pinfunction "FB_5") (pintype "bidirectional"))
      (node (ref "U$56") (pin "2") (pinfunction "2_2") (pintype "passive"))
    )
    (net (code "48") (name "Net-(U$36-OUT)") (class "Default")
      (node (ref "U$36") (pin "6") (pinfunction "OUT_6") (pintype "bidirectional"))
      (node (ref "U$53") (pin "1") (pinfunction "1_1") (pintype "passive"))
      (node (ref "U$56") (pin "1") (pinfunction "1_1") (pintype "passive"))
      (node (ref "U$59") (pin "P$1") (pinfunction "A3_P$1") (pintype "bidirectional"))
    )
    (net (code "49") (name "Net-(U$37-FB)") (class "Default")
      (node (ref "U$37") (pin "5") (pinfunction "FB_5") (pintype "bidirectional"))
      (node (ref "U$57") (pin "2") (pinfunction "2_2") (pintype "passive"))
    )
    (net (code "50") (name "Net-(U$37-OUT)") (class "Default")
      (node (ref "U$37") (pin "6") (pinfunction "OUT_6") (pintype "bidirectional"))
      (node (ref "U$54") (pin "1") (pinfunction "1_1") (pintype "passive"))
      (node (ref "U$57") (pin "1") (pinfunction "1_1") (pintype "passive"))
      (node (ref "U$59") (pin "P$2") (pinfunction "A2_P$2") (pintype "bidirectional"))
    )
    (net (code "51") (name "Net-(U$37-SW)") (class "Default")
      (node (ref "U$37") (pin "1") (pinfunction "SW_1") (pintype "bidirectional"))
      (node (ref "U$47") (pin "P$2") (pinfunction "2_P$2") (pintype "bidirectional"))
      (node (ref "U$50") (pin "2") (pinfunction "2_2") (pintype "passive"))
    )
    (net (code "52") (name "Net-(U$44-FB)") (class "Default")
      (node (ref "U$44") (pin "5") (pinfunction "FB_5") (pintype "bidirectional"))
      (node (ref "U$58") (pin "2") (pinfunction "2_2") (pintype "passive"))
    )
    (net (code "53") (name "Net-(U$44-OUT)") (class "Default")
      (node (ref "U$44") (pin "6") (pinfunction "OUT_6") (pintype "bidirectional"))
      (node (ref "U$55") (pin "1") (pinfunction "1_1") (pintype "passive"))
      (node (ref "U$58") (pin "1") (pinfunction "1_1") (pintype "passive"))
      (node (ref "U$59") (pin "P$3") (pinfunction "A1_P$3") (pintype "bidirectional"))
    )
    (net (code "54") (name "Net-(U$44-SW)") (class "Default")
      (node (ref "U$44") (pin "1") (pinfunction "SW_1") (pintype "bidirectional"))
      (node (ref "U$49") (pin "P$2") (pinfunction "2_P$2") (pintype "bidirectional"))
      (node (ref "U$51") (pin "2") (pinfunction "2_2") (pintype "passive"))
    )
    (net (code "55") (name "Net-(U$62-VIN+)") (class "Default")
      (node (ref "C11") (pin "1") (pinfunction "1_1") (pintype "passive"))
      (node (ref "R12") (pin "1") (pinfunction "1_1") (pintype "passive"))
      (node (ref "U$62") (pin "1") (pinfunction "VIN+_1") (pintype "bidirectional"))
    )
    (net (code "56") (name "Net-(U$62-VIN-)") (class "Default")
      (node (ref "C11") (pin "2") (pinfunction "2_2") (pintype "passive"))
      (node (ref "R13") (pin "1") (pinfunction "1_1") (pintype "passive"))
      (node (ref "U$62") (pin "2") (pinfunction "VIN-_2") (pintype "bidirectional"))
    )
    (net (code "57") (name "Net-(U2-C1+)") (class "Default")
      (node (ref "U$11") (pin "1") (pinfunction "1_1") (pintype "passive"))
      (node (ref "U2") (pin "1") (pinfunction "C1+_1") (pintype "bidirectional"))
    )
    (net (code "58") (name "Net-(U2-C1-)") (class "Default")
      (node (ref "U$11") (pin "2") (pinfunction "2_2") (pintype "passive"))
      (node (ref "U2") (pin "3") (pinfunction "C1-_3") (pintype "bidirectional"))
    )
    (net (code "59") (name "Net-(U2-C2+)") (class "Default")
      (node (ref "U$12") (pin "1") (pinfunction "1_1") (pintype "passive"))
      (node (ref "U2") (pin "4") (pinfunction "C2+_4") (pintype "bidirectional"))
    )
    (net (code "60") (name "Net-(U2-C2-)") (class "Default")
      (node (ref "U$12") (pin "2") (pinfunction "2_2") (pintype "passive"))
      (node (ref "U2") (pin "5") (pinfunction "C2-_5") (pintype "bidirectional"))
    )
    (net (code "61") (name "Net-(U2-V+)") (class "Default")
      (node (ref "U$22") (pin "1") (pinfunction "1_1") (pintype "passive"))
      (node (ref "U2") (pin "2") (pinfunction "V+_2") (pintype "bidirectional"))
    )
    (net (code "62") (name "Net-(U2-V-)") (class "Default")
      (node (ref "U$23") (pin "1") (pinfunction "1_1") (pintype "passive"))
      (node (ref "U2") (pin "6") (pinfunction "V-_6") (pintype "bidirectional"))
    )
    (net (code "63") (name "V+") (class "Default")
      (node (ref "IC1") (pin "3") (pinfunction "IN_3") (pintype "input"))
      (node (ref "R10") (pin "2") (pinfunction "2_2") (pintype "passive"))
      (node (ref "R13") (pin "2") (pinfunction "2_2") (pintype "passive"))
      (node (ref "U$1") (pin "P$2") (pinfunction "ANODE_P$2") (pintype "bidirectional"))
      (node (ref "U$17") (pin "1") (pinfunction "1_1") (pintype "passive"))
      (node (ref "U$2") (pin "P$4") (pinfunction "VDD_P$4") (pintype "bidirectional"))
      (node (ref "U$2") (pin "P$5") (pinfunction "VDDA_P$5") (pintype "bidirectional"))
      (node (ref "U$2") (pin "P$6") (pinfunction "DISP_P$6") (pintype "bidirectional"))
      (node (ref "U$24") (pin "1") (pinfunction "1_1") (pintype "passive"))
      (node (ref "U$31") (pin "2") (pinfunction "2_2") (pintype "passive"))
      (node (ref "U$4") (pin "4") (pinfunction "VIN_4") (pintype "bidirectional"))
      (node (ref "U$5") (pin "4") (pinfunction "VIN_4") (pintype "bidirectional"))
      (node (ref "U$7") (pin "1") (pinfunction "1_1") (pintype "passive"))
      (node (ref "U$8") (pin "14") (pinfunction "VCC_14") (pintype "bidirectional"))
      (node (ref "U3") (pin "8") (pinfunction "VCC_8") (pintype "bidirectional"))
    )
    (net (code "64") (name "unconnected-(POSCON-3-PadP$3)") (class "Default")
      (node (ref "POSCON") (pin "P$3") (pinfunction "3_P$3") (pintype "bidirectional"))
    )
    (net (code "65") (name "unconnected-(POSCON-6-PadP$6)") (class "Default")
      (node (ref "POSCON") (pin "P$6") (pinfunction "6_P$6") (pintype "bidirectional"))
    )
    (net (code "66") (name "unconnected-(SCANNER-7-PadP$7)") (class "Default")
      (node (ref "SCANNER") (pin "P$7") (pinfunction "7_P$7") (pintype "bidirectional"))
    )
    (net (code "67") (name "unconnected-(SCANNER-8-PadP$8)") (class "Default")
      (node (ref "SCANNER") (pin "P$8") (pinfunction "8_P$8") (pintype "bidirectional"))
    )
    (net (code "68") (name "unconnected-(U$3-PadP$7)") (class "Default")
      (node (ref "U$3") (pin "P$7") (pinfunction "P$7_P$7") (pintype "bidirectional"))
    )
    (net (code "69") (name "unconnected-(U$3-PadP$11)") (class "Default")
      (node (ref "U$3") (pin "P$11") (pinfunction "P$11_P$11") (pintype "bidirectional"))
    )
    (net (code "70") (name "unconnected-(U$3-PadP$12)") (class "Default")
      (node (ref "U$3") (pin "P$12") (pinfunction "P$12_P$12") (pintype "bidirectional"))
    )
    (net (code "71") (name "unconnected-(U$3-PadP$13)") (class "Default")
      (node (ref "U$3") (pin "P$13") (pinfunction "P$13_P$13") (pintype "bidirectional"))
    )
    (net (code "72") (name "unconnected-(U$3-PadP$14)") (class "Default")
      (node (ref "U$3") (pin "P$14") (pinfunction "P$14_P$14") (pintype "bidirectional"))
    )
    (net (code "73") (name "unconnected-(U$3-PadP$16)") (class "Default")
      (node (ref "U$3") (pin "P$16") (pinfunction "P$16_P$16") (pintype "bidirectional"))
    )
    (net (code "74") (name "unconnected-(U$3-PadP$18)") (class "Default")
      (node (ref "U$3") (pin "P$18") (pinfunction "P$18_P$18") (pintype "bidirectional"))
    )
    (net (code "75") (name "unconnected-(U$3-PadP$20)") (class "Default")
      (node (ref "U$3") (pin "P$20") (pinfunction "P$20_P$20") (pintype "bidirectional"))
    )
    (net (code "76") (name "unconnected-(U$4-NC-Pad6)") (class "Default")
      (node (ref "U$4") (pin "6") (pinfunction "NC_6") (pintype "bidirectional"))
    )
    (net (code "77") (name "unconnected-(U$5-NC-Pad6)") (class "Default")
      (node (ref "U$5") (pin "6") (pinfunction "NC_6") (pintype "bidirectional"))
    )
    (net (code "78") (name "unconnected-(U$8-CKO-Pad13)") (class "Default")
      (node (ref "U$8") (pin "13") (pinfunction "CKO_13") (pintype "bidirectional"))
    )
    (net (code "79") (name "unconnected-(U$8-NC-Pad11)") (class "Default")
      (node (ref "U$8") (pin "11") (pinfunction "NC_11") (pintype "bidirectional"))
    )
    (net (code "80") (name "unconnected-(U$8-POL-Pad3)") (class "Default")
      (node (ref "U$8") (pin "3") (pinfunction "POL_3") (pintype "bidirectional"))
    )
    (net (code "81") (name "unconnected-(U$8-SDO-Pad12)") (class "Default")
      (node (ref "U$8") (pin "12") (pinfunction "SDO_12") (pintype "bidirectional"))
    )
    (net (code "82") (name "unconnected-(U$9-GNDBREAK-PadP$3)") (class "Default")
      (node (ref "U$9") (pin "P$3") (pinfunction "GNDBREAK_P$3") (pintype "bidirectional"))
    )
    (net (code "83") (name "unconnected-(U$10-NC-PadP$30)") (class "Default")
      (node (ref "U$10") (pin "P$30") (pinfunction "NC_P$30") (pintype "bidirectional"))
    )
    (net (code "84") (name "unconnected-(U$10-NC-PadP$32)") (class "Default")
      (node (ref "U$10") (pin "P$32") (pinfunction "NC_P$32") (pintype "bidirectional"))
    )
    (net (code "85") (name "unconnected-(U$10-NC-PadP$34)") (class "Default")
      (node (ref "U$10") (pin "P$34") (pinfunction "NC_P$34") (pintype "bidirectional"))
    )
    (net (code "86") (name "unconnected-(U$10-NC-PadP$36)") (class "Default")
      (node (ref "U$10") (pin "P$36") (pinfunction "NC_P$36") (pintype "bidirectional"))
    )
    (net (code "87") (name "unconnected-(U$10-PTA19{slash}XTAL0{slash}FTM1_FLT0{slash}FTM_CLKIN1{slash}LPTMR0_ALT1-PadP$20)") (class "Default")
      (node (ref "U$10") (pin "P$20") (pinfunction "PTA19/XTAL0/FTM1_FLT0/FTM_CLKIN1/LPTMR0_ALT1_P$20") (pintype "bidirectional"))
    )
    (net (code "88") (name "unconnected-(U$10-PTC7{slash}CMP0_IN1{slash}SPI0_SIN{slash}USB_SOF_OUT{slash}I2S0_RX_FS-PadP$28)") (class "Default")
      (node (ref "U$10") (pin "P$28") (pinfunction "PTC7/CMP0_IN1/SPI0_SIN/USB_SOF_OUT/I2S0_RX_FS_P$28") (pintype "bidirectional"))
    )
    (net (code "89") (name "unconnected-(U$10-PTD5{slash}ADC0_SE6B{slash}SPI0_PCS2{slash}~{UART0_CTS}{slash}~{UART0_COL}{slash}FTM0_CH5{slash}~{EWM_OUT}-PadP$13)") (class "Default")
      (node (ref "U$10") (pin "P$13") (pinfunction "PTD5/ADC0_SE6B/SPI0_PCS2/~{UART0_CTS}/~{UART0_COL}/FTM0_CH5/~{EWM_OUT}_P$13") (pintype "bidirectional"))
    )
    (net (code "90") (name "unconnected-(U$10-PadP$41)") (class "Default")
      (node (ref "U$10") (pin "P$41") (pinfunction "P$41_P$41") (pintype "bidirectional"))
    )
    (net (code "91") (name "unconnected-(U$10-PadP$42)") (class "Default")
      (node (ref "U$10") (pin "P$42") (pinfunction "P$42_P$42") (pintype "bidirectional"))
    )
    (net (code "92") (name "unconnected-(U$10-VIN-PadP$38)") (class "Default")
      (node (ref "U$10") (pin "P$38") (pinfunction "VIN_P$38") (pintype "bidirectional"))
    )
    (net (code "93") (name "unconnected-(U$10-VIN-PadP$40)") (class "Default")
      (node (ref "U$10") (pin "P$40") (pinfunction "VIN_P$40") (pintype "bidirectional"))
    )
    (net (code "94") (name "unconnected-(U$13-3-PadP$3)") (class "Default")
      (node (ref "U$13") (pin "P$3") (pinfunction "3_P$3") (pintype "input"))
    )
    (net (code "95") (name "unconnected-(U$14-3-PadP$3)") (class "Default")
      (node (ref "U$14") (pin "P$3") (pinfunction "3_P$3") (pintype "input"))
    )
    (net (code "96") (name "unconnected-(U$15-3-PadP$3)") (class "Default")
      (node (ref "U$15") (pin "P$3") (pinfunction "3_P$3") (pintype "input"))
    )
    (net (code "97") (name "unconnected-(U$16-3-PadP$3)") (class "Default")
      (node (ref "U$16") (pin "P$3") (pinfunction "3_P$3") (pintype "input"))
    )
    (net (code "98") (name "unconnected-(U$45-LED1-Pad2)") (class "Default")
      (node (ref "U$45") (pin "2") (pinfunction "LED1_2") (pintype "bidirectional"))
    )
    (net (code "99") (name "unconnected-(U$45-LED2-Pad3)") (class "Default")
      (node (ref "U$45") (pin "3") (pinfunction "LED2_3") (pintype "bidirectional"))
    )
    (net (code "100") (name "unconnected-(U$45-LED3-Pad4)") (class "Default")
      (node (ref "U$45") (pin "4") (pinfunction "LED3_4") (pintype "bidirectional"))
    )
  )
)
